# Smoothiepanel.net
KiCad netlist of a schematic drawn in EAGLE
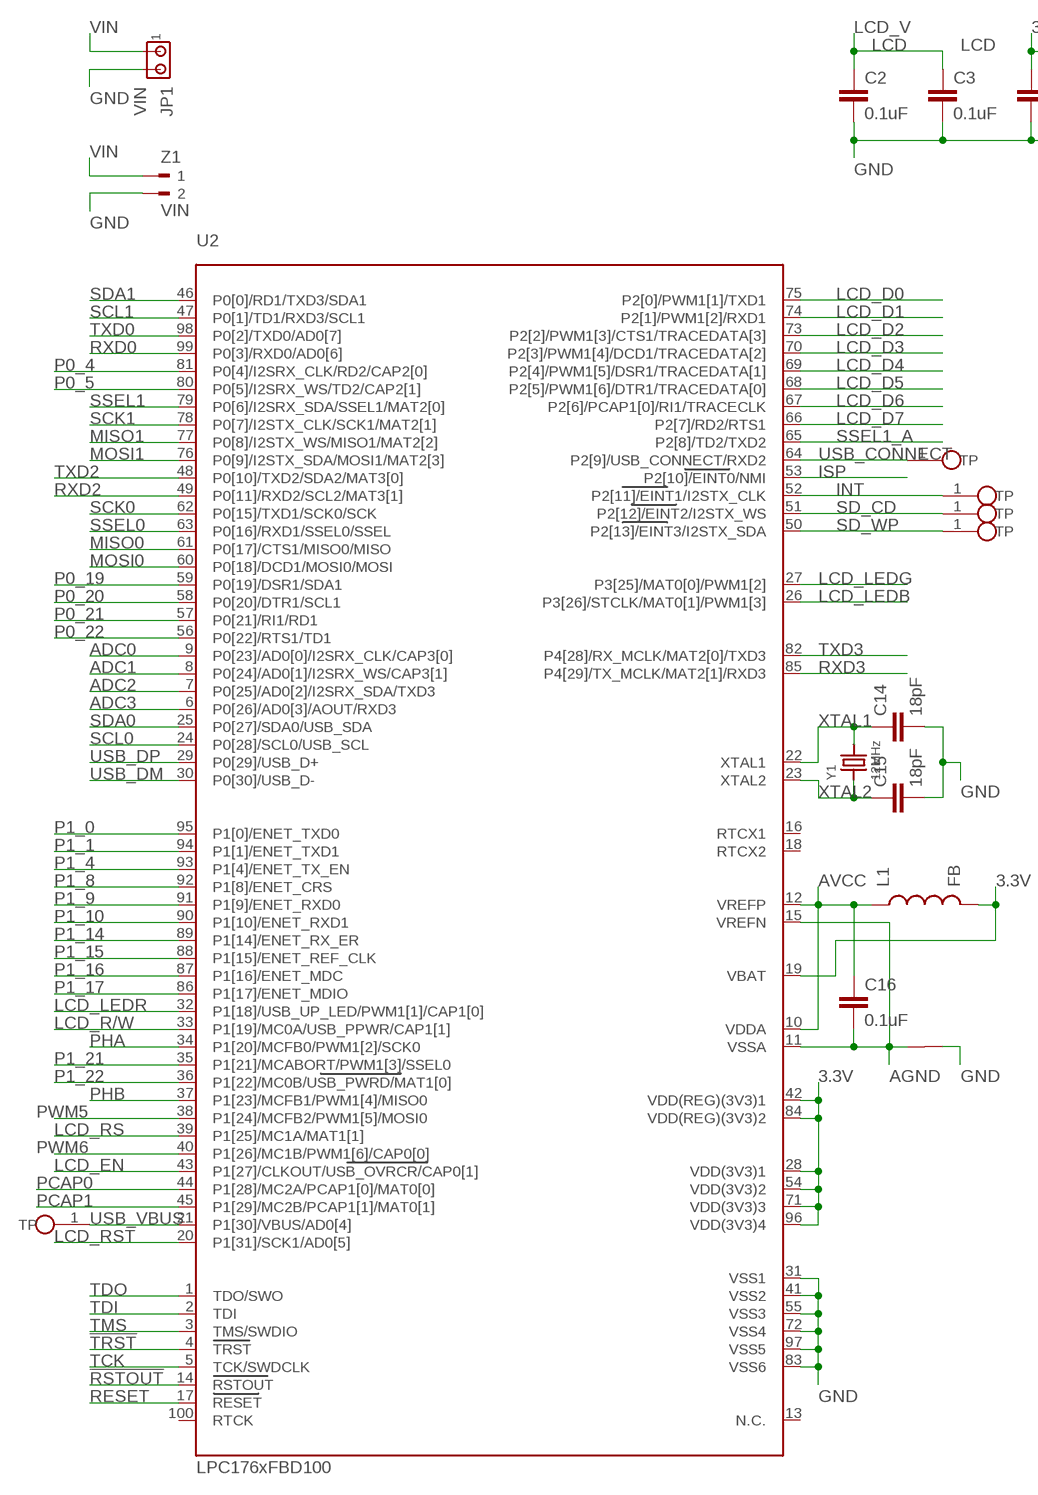
[diagram p0: schematic, sheet 1, part 1 of 2]
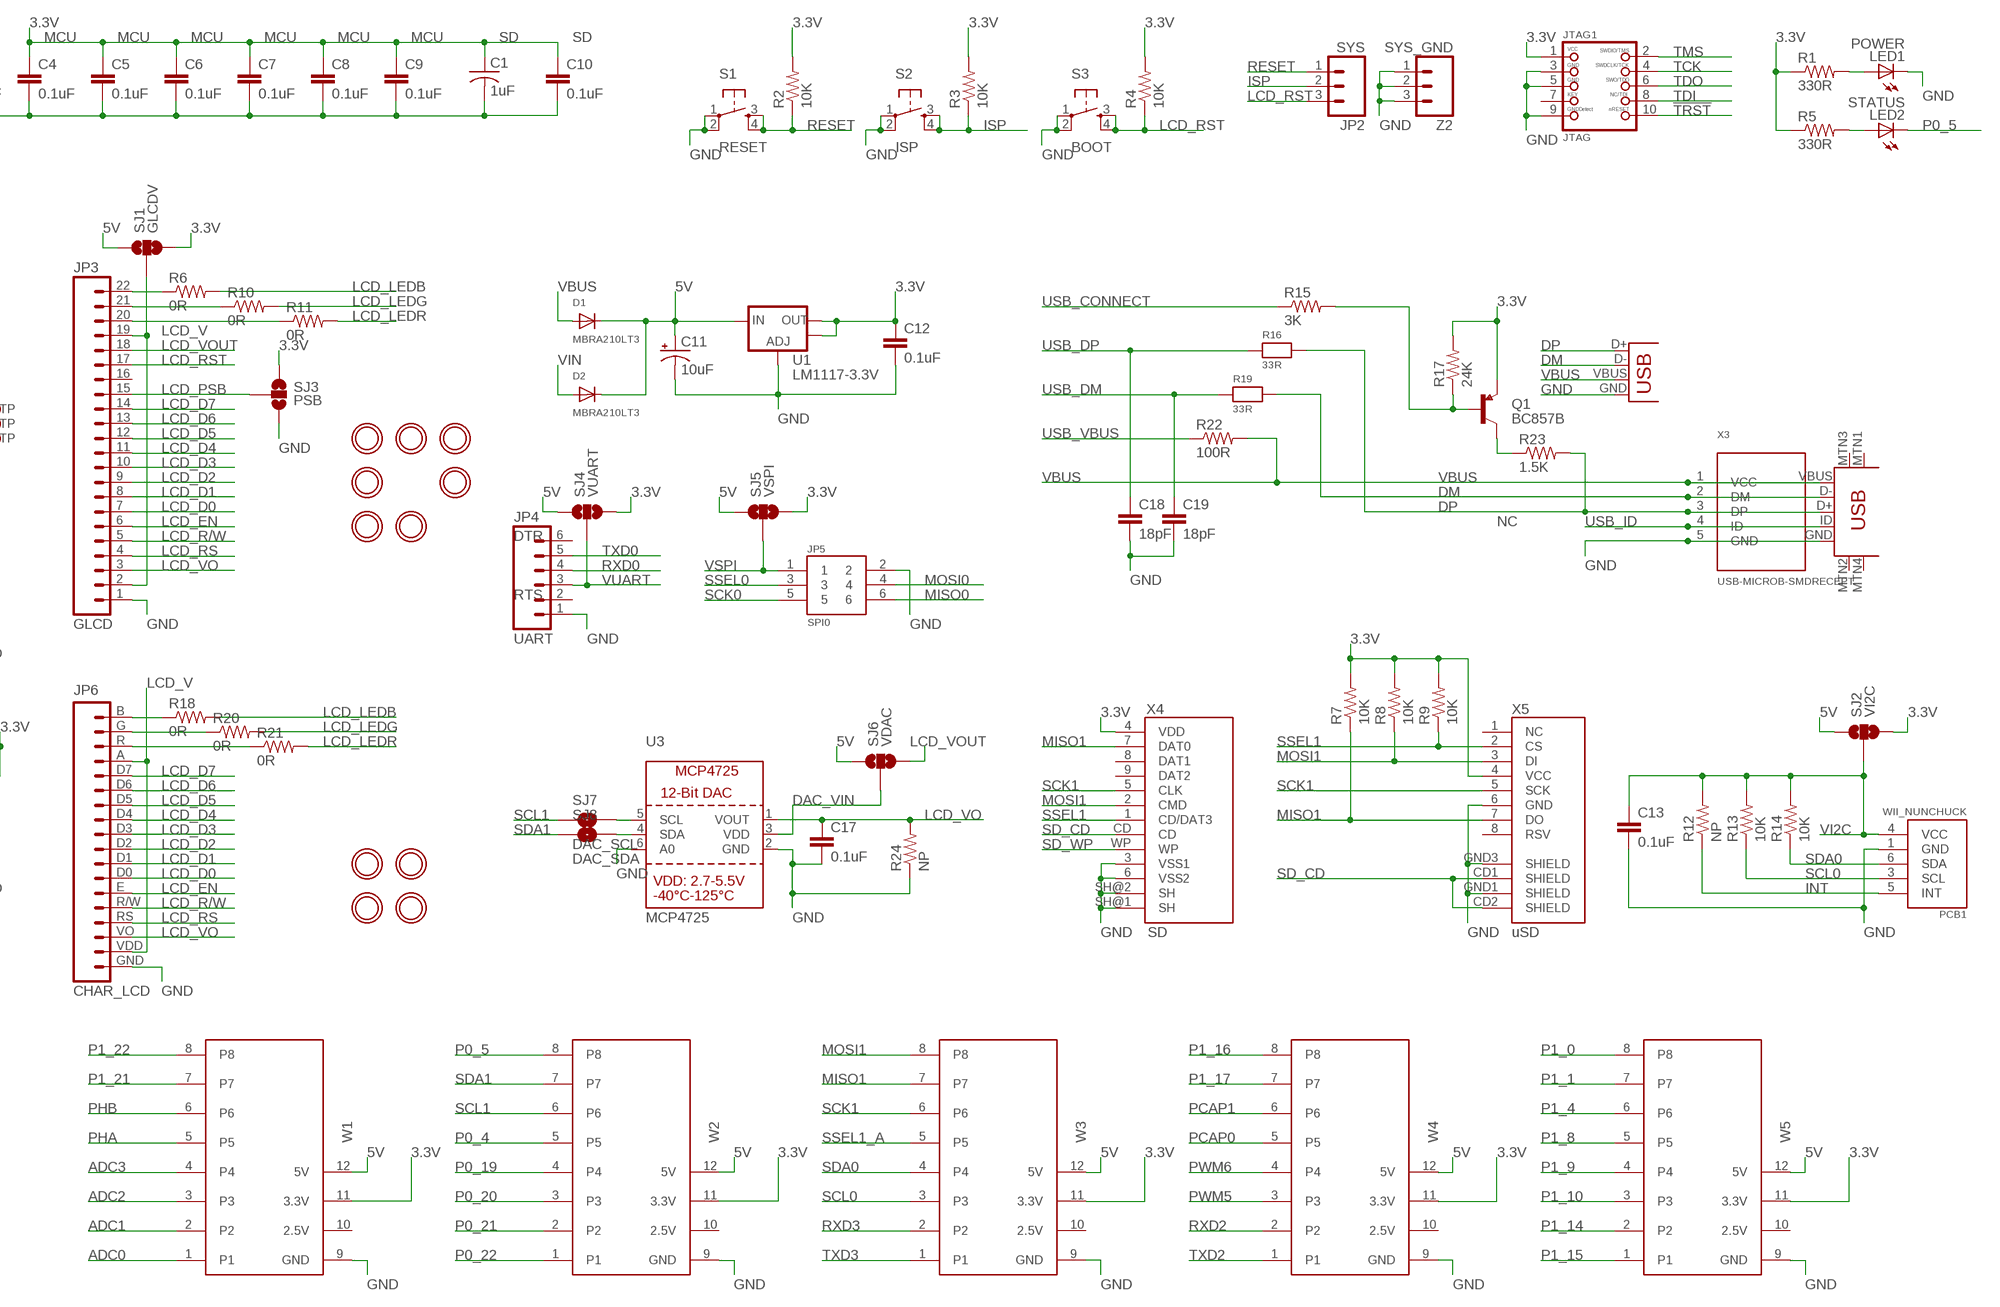
[diagram p1: schematic, sheet 1, part 2 of 2]

(export (version "E")
  (design (tool "Eeschema 10.0.6"))
  (components
    (comp (ref "C1")
      (value "1uF")
      (footprint "eagle-import:C0805")
      (libsource (lib "eagle-import") (part "C-USC0805"))
    )
    (comp (ref "C2")
      (value "0.1uF")
      (footprint "eagle-import:0603-CAP")
      (libsource (lib "eagle-import") (part "CAP0603-CAP"))
    )
    (comp (ref "C3")
      (value "0.1uF")
      (footprint "eagle-import:0603-CAP")
      (libsource (lib "eagle-import") (part "CAP0603-CAP"))
    )
    (comp (ref "C4")
      (value "0.1uF")
      (footprint "eagle-import:0603-CAP")
      (libsource (lib "eagle-import") (part "CAP0603-CAP"))
    )
    (comp (ref "C5")
      (value "0.1uF")
      (footprint "eagle-import:0603-CAP")
      (libsource (lib "eagle-import") (part "CAP0603-CAP"))
    )
    (comp (ref "C6")
      (value "0.1uF")
      (footprint "eagle-import:0603-CAP")
      (libsource (lib "eagle-import") (part "CAP0603-CAP"))
    )
    (comp (ref "C7")
      (value "0.1uF")
      (footprint "eagle-import:0603-CAP")
      (libsource (lib "eagle-import") (part "CAP0603-CAP"))
    )
    (comp (ref "C8")
      (value "0.1uF")
      (footprint "eagle-import:0603-CAP")
      (libsource (lib "eagle-import") (part "CAP0603-CAP"))
    )
    (comp (ref "C9")
      (value "0.1uF")
      (footprint "eagle-import:0603-CAP")
      (libsource (lib "eagle-import") (part "CAP0603-CAP"))
    )
    (comp (ref "C10")
      (value "0.1uF")
      (footprint "eagle-import:0603-CAP")
      (libsource (lib "eagle-import") (part "CAP0603-CAP"))
    )
    (comp (ref "C11")
      (value "10uF")
      (footprint "eagle-import:EIA3216")
      (libsource (lib "eagle-import") (part "CAP_POL1206"))
    )
    (comp (ref "C12")
      (value "0.1uF")
      (footprint "eagle-import:0603-CAP")
      (libsource (lib "eagle-import") (part "CAP0603-CAP"))
    )
    (comp (ref "C13")
      (value "0.1uF")
      (footprint "eagle-import:0603-CAP")
      (libsource (lib "eagle-import") (part "CAP0603-CAP"))
    )
    (comp (ref "C14")
      (value "18pF")
      (footprint "eagle-import:0603-CAP")
      (libsource (lib "eagle-import") (part "SparkFun-Passives_CAP0603-CAP"))
    )
    (comp (ref "C15")
      (value "18pF")
      (footprint "eagle-import:0603-CAP")
      (libsource (lib "eagle-import") (part "SparkFun-Passives_CAP0603-CAP"))
    )
    (comp (ref "C16")
      (value "0.1uF")
      (footprint "eagle-import:0603-CAP")
      (libsource (lib "eagle-import") (part "CAP0603-CAP"))
    )
    (comp (ref "C17")
      (value "0.1uF")
      (footprint "eagle-import:0603-CAP")
      (libsource (lib "eagle-import") (part "CAP0603-CAP"))
    )
    (comp (ref "C18")
      (value "18pF")
      (footprint "eagle-import:0603-CAP")
      (libsource (lib "eagle-import") (part "CAP0603-CAP"))
    )
    (comp (ref "C19")
      (value "18pF")
      (footprint "eagle-import:0603-CAP")
      (libsource (lib "eagle-import") (part "CAP0603-CAP"))
    )
    (comp (ref "D1")
      (value "MBRA210LT3")
      (footprint "eagle-import:SMADIODE")
      (libsource (lib "eagle-import") (part "DIODESMA"))
    )
    (comp (ref "D2")
      (value "MBRA210LT3")
      (footprint "eagle-import:SMADIODE")
      (libsource (lib "eagle-import") (part "DIODESMA"))
    )
    (comp (ref "JP1")
      (value "VIN")
      (footprint "eagle-import:10X02MTA")
      (libsource (lib "eagle-import") (part "MTA02-100"))
    )
    (comp (ref "JP2")
      (value "SYS")
      (footprint "eagle-import:1X03")
      (libsource (lib "eagle-import") (part "M03PTH"))
    )
    (comp (ref "JP3")
      (value "GLCD")
      (footprint "eagle-import:1X22")
      (libsource (lib "eagle-import") (part "M22"))
    )
    (comp (ref "JP4")
      (value "UART")
      (footprint "eagle-import:1X06")
      (libsource (lib "eagle-import") (part "M06SIP"))
    )
    (comp (ref "JP5")
      (value "SPI0")
      (footprint "eagle-import:2X3-SHROUDED")
      (libsource (lib "eagle-import") (part "M03X2"))
    )
    (comp (ref "JP6")
      (value "CHAR_LCD")
      (footprint "eagle-import:TEXT_LCD")
      (libsource (lib "eagle-import") (part "LCD_TEXT"))
    )
    (comp (ref "JTAG1")
      (value "JTAG")
      (footprint "eagle-import:2X05_1.27MM_SMT")
      (libsource (lib "eagle-import") (part "JTAG-CORTEXM3"))
    )
    (comp (ref "L1")
      (value "FB")
      (footprint "eagle-import:0603")
      (libsource (lib "eagle-import") (part "INDUCTOR0603"))
    )
    (comp (ref "LED1")
      (value "POWER")
      (footprint "eagle-import:LED-0603")
      (libsource (lib "eagle-import") (part "LED0603"))
    )
    (comp (ref "LED2")
      (value "STATUS")
      (footprint "eagle-import:LED-0603")
      (libsource (lib "eagle-import") (part "LED0603"))
    )
    (comp (ref "MH1")
      (value "MOUNTINGHOLE2.5_THICK")
      (footprint "eagle-import:MOUNTINGHOLE_2.5_PLATED_THICK")
      (libsource (lib "eagle-import") (part "MOUNTINGHOLE2.5_THICK"))
    )
    (comp (ref "MH2")
      (value "MOUNTINGHOLE2.5_THICK")
      (footprint "eagle-import:MOUNTINGHOLE_2.5_PLATED_THICK")
      (libsource (lib "eagle-import") (part "MOUNTINGHOLE2.5_THICK"))
    )
    (comp (ref "MH3")
      (value "MOUNTINGHOLE2.5_THICK")
      (footprint "eagle-import:MOUNTINGHOLE_2.5_PLATED_THICK")
      (libsource (lib "eagle-import") (part "MOUNTINGHOLE2.5_THICK"))
    )
    (comp (ref "MH4")
      (value "MOUNTINGHOLE2.5_THICK")
      (footprint "eagle-import:MOUNTINGHOLE_2.5_PLATED_THICK")
      (libsource (lib "eagle-import") (part "MOUNTINGHOLE2.5_THICK"))
    )
    (comp (ref "MH5")
      (value "MOUNTINGHOLE2.5_THICK")
      (footprint "eagle-import:MOUNTINGHOLE_2.5_PLATED_THICK")
      (libsource (lib "eagle-import") (part "MOUNTINGHOLE2.5_THICK"))
    )
    (comp (ref "MH6")
      (value "MOUNTINGHOLE2.5_THICK")
      (footprint "eagle-import:MOUNTINGHOLE_2.5_PLATED_THICK")
      (libsource (lib "eagle-import") (part "MOUNTINGHOLE2.5_THICK"))
    )
    (comp (ref "MH7")
      (value "MOUNTINGHOLE2.5_THICK")
      (footprint "eagle-import:MOUNTINGHOLE_2.5_PLATED_THICK")
      (libsource (lib "eagle-import") (part "MOUNTINGHOLE2.5_THICK"))
    )
    (comp (ref "MH8")
      (value "MOUNTINGHOLE3.0THIN")
      (footprint "eagle-import:MOUNTINGHOLE_3.0_PLATEDTHIN")
      (libsource (lib "eagle-import") (part "MOUNTINGHOLE3.0THIN"))
    )
    (comp (ref "MH9")
      (value "MOUNTINGHOLE3.0THIN")
      (footprint "eagle-import:MOUNTINGHOLE_3.0_PLATEDTHIN")
      (libsource (lib "eagle-import") (part "MOUNTINGHOLE3.0THIN"))
    )
    (comp (ref "MH10")
      (value "MOUNTINGHOLE3.0THIN")
      (footprint "eagle-import:MOUNTINGHOLE_3.0_PLATEDTHIN")
      (libsource (lib "eagle-import") (part "MOUNTINGHOLE3.0THIN"))
    )
    (comp (ref "MH11")
      (value "MOUNTINGHOLE3.0THIN")
      (footprint "eagle-import:MOUNTINGHOLE_3.0_PLATEDTHIN")
      (libsource (lib "eagle-import") (part "MOUNTINGHOLE3.0THIN"))
    )
    (comp (ref "N1")
      (value "NET_LINK")
      (footprint "eagle-import:NET_LINK")
      (libsource (lib "eagle-import") (part "NET_LINK"))
    )
    (comp (ref "PCB1")
      (value "WII_NUNCHUCK")
      (footprint "eagle-import:WII_NUNCHUCK")
      (libsource (lib "eagle-import") (part "WII_NUNCHUCK"))
    )
    (comp (ref "Q1")
      (value "BC857B")
      (footprint "eagle-import:SOT23-3")
      (libsource (lib "eagle-import") (part "TRANSISTOR_PNPSMD"))
    )
    (comp (ref "R1")
      (value "330R")
      (footprint "eagle-import:0603-RES")
      (libsource (lib "eagle-import") (part "SparkFun-Resistors_RESISTOR0603-RES"))
    )
    (comp (ref "R2")
      (value "10K")
      (footprint "eagle-import:0603-RES")
      (libsource (lib "eagle-import") (part "SparkFun-Resistors_RESISTOR0603-RES"))
    )
    (comp (ref "R3")
      (value "10K")
      (footprint "eagle-import:0603-RES")
      (libsource (lib "eagle-import") (part "SparkFun-Resistors_RESISTOR0603-RES"))
    )
    (comp (ref "R4")
      (value "10K")
      (footprint "eagle-import:0603-RES")
      (libsource (lib "eagle-import") (part "SparkFun-Resistors_RESISTOR0603-RES"))
    )
    (comp (ref "R5")
      (value "330R")
      (footprint "eagle-import:0603-RES")
      (libsource (lib "eagle-import") (part "SparkFun-Resistors_RESISTOR0603-RES"))
    )
    (comp (ref "R6")
      (value "0R")
      (footprint "eagle-import:0603-RES")
      (libsource (lib "eagle-import") (part "SparkFun-Resistors_RESISTOR0603-RES"))
    )
    (comp (ref "R7")
      (value "10K")
      (footprint "eagle-import:0603-RES")
      (libsource (lib "eagle-import") (part "SparkFun-Resistors_RESISTOR0603-RES"))
    )
    (comp (ref "R8")
      (value "10K")
      (footprint "eagle-import:0603-RES")
      (libsource (lib "eagle-import") (part "SparkFun-Resistors_RESISTOR0603-RES"))
    )
    (comp (ref "R9")
      (value "10K")
      (footprint "eagle-import:0603-RES")
      (libsource (lib "eagle-import") (part "SparkFun-Resistors_RESISTOR0603-RES"))
    )
    (comp (ref "R10")
      (value "0R")
      (footprint "eagle-import:0603-RES")
      (libsource (lib "eagle-import") (part "SparkFun-Resistors_RESISTOR0603-RES"))
    )
    (comp (ref "R11")
      (value "0R")
      (footprint "eagle-import:0603-RES")
      (libsource (lib "eagle-import") (part "SparkFun-Resistors_RESISTOR0603-RES"))
    )
    (comp (ref "R12")
      (value "NP")
      (footprint "eagle-import:0603-RES")
      (libsource (lib "eagle-import") (part "RESISTOR0603-RES"))
    )
    (comp (ref "R13")
      (value "10K")
      (footprint "eagle-import:0603-RES")
      (libsource (lib "eagle-import") (part "SparkFun-Resistors_RESISTOR0603-RES"))
    )
    (comp (ref "R14")
      (value "10K")
      (footprint "eagle-import:0603-RES")
      (libsource (lib "eagle-import") (part "SparkFun-Resistors_RESISTOR0603-RES"))
    )
    (comp (ref "R15")
      (value "3K")
      (footprint "eagle-import:0603-RES")
      (libsource (lib "eagle-import") (part "SparkFun-Resistors_RESISTOR0603-RES"))
    )
    (comp (ref "R16")
      (value "33R")
      (footprint "eagle-import:_0603MP")
      (libsource (lib "eagle-import") (part "RESISTOR_0603MP"))
    )
    (comp (ref "R17")
      (value "24K")
      (footprint "eagle-import:0603-RES")
      (libsource (lib "eagle-import") (part "SparkFun-Resistors_RESISTOR0603-RES"))
    )
    (comp (ref "R18")
      (value "0R")
      (footprint "eagle-import:0603-RES")
      (libsource (lib "eagle-import") (part "RESISTOR0603-RES"))
    )
    (comp (ref "R19")
      (value "33R")
      (footprint "eagle-import:_0603MP")
      (libsource (lib "eagle-import") (part "RESISTOR_0603MP"))
    )
    (comp (ref "R20")
      (value "0R")
      (footprint "eagle-import:0603-RES")
      (libsource (lib "eagle-import") (part "RESISTOR0603-RES"))
    )
    (comp (ref "R21")
      (value "0R")
      (footprint "eagle-import:0603-RES")
      (libsource (lib "eagle-import") (part "RESISTOR0603-RES"))
    )
    (comp (ref "R22")
      (value "100R")
      (footprint "eagle-import:0603-RES")
      (libsource (lib "eagle-import") (part "SparkFun-Resistors_RESISTOR0603-RES"))
    )
    (comp (ref "R23")
      (value "1.5K")
      (footprint "eagle-import:0603-RES")
      (libsource (lib "eagle-import") (part "SparkFun-Resistors_RESISTOR0603-RES"))
    )
    (comp (ref "R24")
      (value "NP")
      (footprint "eagle-import:0603-RES")
      (libsource (lib "eagle-import") (part "SparkFun-Resistors_RESISTOR0603-RES"))
    )
    (comp (ref "S1")
      (value "RESET")
      (footprint "eagle-import:TACTILE_SWITCH_SMD")
      (libsource (lib "eagle-import") (part "TAC_SWITCHSMD"))
    )
    (comp (ref "S2")
      (value "ISP")
      (footprint "eagle-import:TACTILE_SWITCH_SMD")
      (libsource (lib "eagle-import") (part "TAC_SWITCHSMD"))
    )
    (comp (ref "S3")
      (value "BOOT")
      (footprint "eagle-import:TACTILE_SWITCH_SMD")
      (libsource (lib "eagle-import") (part "TAC_SWITCHSMD"))
    )
    (comp (ref "SJ1")
      (value "GLCDV")
      (footprint "eagle-import:SJ_3")
      (libsource (lib "eagle-import") (part "SOLDERJUMPER_2WAYS"))
    )
    (comp (ref "SJ2")
      (value "VI2C")
      (footprint "eagle-import:SJ_3")
      (libsource (lib "eagle-import") (part "SparkFun-Passives_SOLDERJUMPER_2WAYS"))
    )
    (comp (ref "SJ3")
      (value "PSB")
      (footprint "eagle-import:SJ_3")
      (libsource (lib "eagle-import") (part "SOLDERJUMPER_2WAYS"))
    )
    (comp (ref "SJ4")
      (value "VUART")
      (footprint "eagle-import:SJ_3")
      (libsource (lib "eagle-import") (part "SOLDERJUMPER_2WAYS"))
    )
    (comp (ref "SJ5")
      (value "VSPI")
      (footprint "eagle-import:SJ_3")
      (libsource (lib "eagle-import") (part "SOLDERJUMPER_2WAYS"))
    )
    (comp (ref "SJ6")
      (value "VDAC")
      (footprint "eagle-import:SJ_3")
      (libsource (lib "eagle-import") (part "SOLDERJUMPER_2WAYS"))
    )
    (comp (ref "SJ7")
      (value "DAC_SCL")
      (footprint "eagle-import:SJ_2S-TRACE")
      (libsource (lib "eagle-import") (part "SOLDERJUMPERTRACE"))
    )
    (comp (ref "SJ8")
      (value "DAC_SDA")
      (footprint "eagle-import:SJ_2S-TRACE")
      (libsource (lib "eagle-import") (part "SOLDERJUMPERTRACE"))
    )
    (comp (ref "TP1")
      (value "TPAD1.5")
      (footprint "eagle-import:TPAD-1.5")
      (libsource (lib "eagle-import") (part "TPAD1.5"))
    )
    (comp (ref "TP3")
      (value "TPAD1.5")
      (footprint "eagle-import:TPAD-1.5")
      (libsource (lib "eagle-import") (part "TPAD1.5"))
    )
    (comp (ref "TP4")
      (value "TPAD1.5")
      (footprint "eagle-import:TPAD-1.5")
      (libsource (lib "eagle-import") (part "TPAD1.5"))
    )
    (comp (ref "TP5")
      (value "TPAD1.5")
      (footprint "eagle-import:TPAD-1.5")
      (libsource (lib "eagle-import") (part "TPAD1.5"))
    )
    (comp (ref "TP6")
      (value "TPAD1.5")
      (footprint "eagle-import:TPAD-1.5")
      (libsource (lib "eagle-import") (part "TPAD1.5"))
    )
    (comp (ref "U1")
      (value "LM1117-3.3V")
      (footprint "eagle-import:SOT223")
      (libsource (lib "eagle-import") (part "V_REG_LM1117SOT223"))
    )
    (comp (ref "U2")
      (value "LPC176xFBD100")
      (footprint "eagle-import:LQFP100")
      (libsource (lib "eagle-import") (part "LPC1768"))
    )
    (comp (ref "U3")
      (value "MCP4725")
      (footprint "eagle-import:SOT23-6")
      (libsource (lib "eagle-import") (part "DAC_MCP4725"))
    )
    (comp (ref "W1")
      (value "WING1")
      (footprint "eagle-import:PAPILIO-WING-8BITS-F")
      (libsource (lib "eagle-import") (part "PAPILIO-WING-8BITSF"))
    )
    (comp (ref "W2")
      (value "WING2")
      (footprint "eagle-import:PAPILIO-WING-8BITS-F")
      (libsource (lib "eagle-import") (part "PAPILIO-WING-8BITSF"))
    )
    (comp (ref "W3")
      (value "WING3")
      (footprint "eagle-import:PAPILIO-WING-8BITS-F")
      (libsource (lib "eagle-import") (part "PAPILIO-WING-8BITSF"))
    )
    (comp (ref "W4")
      (value "WING4")
      (footprint "eagle-import:PAPILIO-WING-8BITS-F")
      (libsource (lib "eagle-import") (part "PAPILIO-WING-8BITSF"))
    )
    (comp (ref "W5")
      (value "WING5")
      (footprint "eagle-import:PAPILIO-WING-8BITS-F")
      (libsource (lib "eagle-import") (part "PAPILIO-WING-8BITSF"))
    )
    (comp (ref "X1")
      (value "USB-B")
      (footprint "eagle-import:USB-B-PTH")
      (libsource (lib "eagle-import") (part "USBPTH"))
    )
    (comp (ref "X2")
      (value "mUSB")
      (footprint "eagle-import:USB-MINIB")
      (libsource (lib "eagle-import") (part "USB-MINIB-5PIN"))
    )
    (comp (ref "X3")
      (value "USB-MICROB-SMDRECEPT")
      (footprint "eagle-import:USB-MICROB-RECEPT")
      (libsource (lib "eagle-import") (part "USB-MICROB-SMDRECEPT"))
    )
    (comp (ref "X4")
      (value "SD")
      (footprint "eagle-import:SDCARD_4UCONN")
      (libsource (lib "eagle-import") (part "SD_CARD_SOCKET4UCON"))
    )
    (comp (ref "X5")
      (value "uSD")
      (footprint "eagle-import:MICRO-SD-SOCKET-PP")
      (libsource (lib "eagle-import") (part "USD-SOCKETNEW"))
    )
    (comp (ref "Y1")
      (value "12MHz")
      (footprint "eagle-import:CRYSTAL_3.2X2.5")
      (libsource (lib "eagle-import") (part "CRYSTALTHIN"))
    )
    (comp (ref "Z1")
      (value "VIN")
      (footprint "eagle-import:180-2")
      (libsource (lib "eagle-import") (part "180-2"))
    )
    (comp (ref "Z2")
      (value "SYS_GND")
      (footprint "eagle-import:1X03")
      (libsource (lib "eagle-import") (part "M03PTH"))
    )
  )
  (nets
    (net (code "1") (name "/3.3V") (class "Default")
      (node (ref "C1") (pin "1") (pinfunction "1_1") (pintype "passive"))
      (node (ref "C10") (pin "1") (pinfunction "1_1") (pintype "passive"))
      (node (ref "C12") (pin "1") (pinfunction "1_1") (pintype "passive"))
      (node (ref "C4") (pin "1") (pinfunction "1_1") (pintype "passive"))
      (node (ref "C5") (pin "1") (pinfunction "1_1") (pintype "passive"))
      (node (ref "C6") (pin "1") (pinfunction "1_1") (pintype "passive"))
      (node (ref "C7") (pin "1") (pinfunction "1_1") (pintype "passive"))
      (node (ref "C8") (pin "1") (pinfunction "1_1") (pintype "passive"))
      (node (ref "C9") (pin "1") (pinfunction "1_1") (pintype "passive"))
      (node (ref "JTAG1") (pin "1") (pinfunction "1_1") (pintype "passive"))
      (node (ref "L1") (pin "2") (pinfunction "2_2") (pintype "passive"))
      (node (ref "Q1") (pin "2") (pinfunction "E_2") (pintype "passive"))
      (node (ref "R1") (pin "1") (pinfunction "1_1") (pintype "passive"))
      (node (ref "R17") (pin "2") (pinfunction "2_2") (pintype "passive"))
      (node (ref "R2") (pin "2") (pinfunction "2_2") (pintype "passive"))
      (node (ref "R3") (pin "2") (pinfunction "2_2") (pintype "passive"))
      (node (ref "R4") (pin "2") (pinfunction "2_2") (pintype "passive"))
      (node (ref "R5") (pin "1") (pinfunction "1_1") (pintype "passive"))
      (node (ref "R7") (pin "2") (pinfunction "2_2") (pintype "passive"))
      (node (ref "R8") (pin "2") (pinfunction "2_2") (pintype "passive"))
      (node (ref "R9") (pin "2") (pinfunction "2_2") (pintype "passive"))
      (node (ref "SJ1") (pin "3") (pinfunction "3_3") (pintype "passive"))
      (node (ref "SJ2") (pin "3") (pinfunction "3_3") (pintype "passive"))
      (node (ref "SJ3") (pin "1") (pinfunction "1_1") (pintype "passive"))
      (node (ref "SJ4") (pin "3") (pinfunction "3_3") (pintype "passive"))
      (node (ref "SJ5") (pin "3") (pinfunction "3_3") (pintype "passive"))
      (node (ref "U1") (pin "2") (pinfunction "OUT_2") (pintype "output"))
      (node (ref "U1") (pin "4") (pinfunction "OUT_4") (pintype "output"))
      (node (ref "U2") (pin "19") (pinfunction "VBAT_19") (pintype "power_in"))
      (node (ref "U2") (pin "28") (pinfunction "VDD(3V3)1_28") (pintype "power_in"))
      (node (ref "U2") (pin "42") (pinfunction "VDD(REG)(3V3)1_42") (pintype "power_in"))
      (node (ref "U2") (pin "54") (pinfunction "VDD(3V3)2_54") (pintype "power_in"))
      (node (ref "U2") (pin "71") (pinfunction "VDD(3V3)3_71") (pintype "power_in"))
      (node (ref "U2") (pin "84") (pinfunction "VDD(REG)(3V3)2_84") (pintype "power_in"))
      (node (ref "U2") (pin "96") (pinfunction "VDD(3V3)4_96") (pintype "power_in"))
      (node (ref "W1") (pin "11") (pinfunction "3.3V_11") (pintype "bidirectional"))
      (node (ref "W2") (pin "11") (pinfunction "3.3V_11") (pintype "bidirectional"))
      (node (ref "W3") (pin "11") (pinfunction "3.3V_11") (pintype "bidirectional"))
      (node (ref "W4") (pin "11") (pinfunction "3.3V_11") (pintype "bidirectional"))
      (node (ref "W5") (pin "11") (pinfunction "3.3V_11") (pintype "bidirectional"))
      (node (ref "X4") (pin "4") (pinfunction "VDD_4") (pintype "power_in"))
      (node (ref "X5") (pin "4") (pinfunction "VCC_4") (pintype "bidirectional"))
    )
    (net (code "2") (name "/5V") (class "Default")
      (node (ref "C11") (pin "A") (pinfunction "+_A") (pintype "passive"))
      (node (ref "D1") (pin "C") (pinfunction "C_C") (pintype "passive"))
      (node (ref "D2") (pin "C") (pinfunction "C_C") (pintype "passive"))
      (node (ref "SJ1") (pin "1") (pinfunction "1_1") (pintype "passive"))
      (node (ref "SJ2") (pin "1") (pinfunction "1_1") (pintype "passive"))
      (node (ref "SJ4") (pin "1") (pinfunction "1_1") (pintype "passive"))
      (node (ref "SJ5") (pin "1") (pinfunction "1_1") (pintype "passive"))
      (node (ref "SJ6") (pin "1") (pinfunction "1_1") (pintype "passive"))
      (node (ref "U1") (pin "3") (pinfunction "IN_3") (pintype "input"))
      (node (ref "W1") (pin "12") (pinfunction "5V_12") (pintype "bidirectional"))
      (node (ref "W2") (pin "12") (pinfunction "5V_12") (pintype "bidirectional"))
      (node (ref "W3") (pin "12") (pinfunction "5V_12") (pintype "bidirectional"))
      (node (ref "W4") (pin "12") (pinfunction "5V_12") (pintype "bidirectional"))
      (node (ref "W5") (pin "12") (pinfunction "5V_12") (pintype "bidirectional"))
    )
    (net (code "3") (name "/ADC0") (class "Default")
      (node (ref "U2") (pin "9") (pinfunction "P0[23]/AD0[0]/I2SRX_CLK/CAP3[0]_9") (pintype "bidirectional"))
      (node (ref "W1") (pin "1") (pinfunction "P1_1") (pintype "bidirectional"))
    )
    (net (code "4") (name "/ADC1") (class "Default")
      (node (ref "U2") (pin "8") (pinfunction "P0[24]/AD0[1]/I2SRX_WS/CAP3[1]_8") (pintype "bidirectional"))
      (node (ref "W1") (pin "2") (pinfunction "P2_2") (pintype "bidirectional"))
    )
    (net (code "5") (name "/ADC2") (class "Default")
      (node (ref "U2") (pin "7") (pinfunction "P0[25]/AD0[2]/I2SRX_SDA/TXD3_7") (pintype "bidirectional"))
      (node (ref "W1") (pin "3") (pinfunction "P3_3") (pintype "bidirectional"))
    )
    (net (code "6") (name "/ADC3") (class "Default")
      (node (ref "U2") (pin "6") (pinfunction "P0[26]/AD0[3]/AOUT/RXD3_6") (pintype "bidirectional"))
      (node (ref "W1") (pin "4") (pinfunction "P4_4") (pintype "bidirectional"))
    )
    (net (code "7") (name "/AGND") (class "Default")
      (node (ref "C16") (pin "2") (pinfunction "2_2") (pintype "passive"))
      (node (ref "N1") (pin "P$1") (pinfunction "P$1_P$1") (pintype "bidirectional"))
      (node (ref "U2") (pin "11") (pinfunction "VSSA_11") (pintype "power_in"))
      (node (ref "U2") (pin "15") (pinfunction "VREFN_15") (pintype "power_in"))
    )
    (net (code "8") (name "/AVCC") (class "Default")
      (node (ref "C16") (pin "1") (pinfunction "1_1") (pintype "passive"))
      (node (ref "L1") (pin "1") (pinfunction "1_1") (pintype "passive"))
      (node (ref "U2") (pin "10") (pinfunction "VDDA_10") (pintype "power_in"))
      (node (ref "U2") (pin "12") (pinfunction "VREFP_12") (pintype "power_in"))
    )
    (net (code "9") (name "/DAC_VIN") (class "Default")
      (node (ref "SJ6") (pin "2") (pinfunction "2_2") (pintype "passive"))
      (node (ref "U3") (pin "3") (pinfunction "VDD_3") (pintype "power_in"))
    )
    (net (code "10") (name "/DM") (class "Default")
      (node (ref "R19") (pin "2") (pinfunction "2_2") (pintype "passive"))
      (node (ref "X1") (pin "D-") (pinfunction "D-_D-") (pintype "bidirectional"))
      (node (ref "X2") (pin "D-") (pinfunction "D-_D-") (pintype "bidirectional"))
      (node (ref "X3") (pin "2") (pinfunction "DM_2") (pintype "bidirectional"))
    )
    (net (code "11") (name "/DP") (class "Default")
      (node (ref "R16") (pin "2") (pinfunction "2_2") (pintype "passive"))
      (node (ref "R23") (pin "2") (pinfunction "2_2") (pintype "passive"))
      (node (ref "X1") (pin "D+") (pinfunction "D+_D+") (pintype "bidirectional"))
      (node (ref "X2") (pin "D+") (pinfunction "D+_D+") (pintype "bidirectional"))
      (node (ref "X3") (pin "3") (pinfunction "DP_3") (pintype "bidirectional"))
    )
    (net (code "12") (name "/GND") (class "Default")
      (node (ref "C1") (pin "2") (pinfunction "2_2") (pintype "passive"))
      (node (ref "C10") (pin "2") (pinfunction "2_2") (pintype "passive"))
      (node (ref "C11") (pin "C") (pinfunction "-_C") (pintype "passive"))
      (node (ref "C12") (pin "2") (pinfunction "2_2") (pintype "passive"))
      (node (ref "C13") (pin "2") (pinfunction "2_2") (pintype "passive"))
      (node (ref "C14") (pin "2") (pinfunction "2_2") (pintype "passive"))
      (node (ref "C15") (pin "2") (pinfunction "2_2") (pintype "passive"))
      (node (ref "C17") (pin "2") (pinfunction "2_2") (pintype "passive"))
      (node (ref "C18") (pin "2") (pinfunction "2_2") (pintype "passive"))
      (node (ref "C19") (pin "2") (pinfunction "2_2") (pintype "passive"))
      (node (ref "C2") (pin "2") (pinfunction "2_2") (pintype "passive"))
      (node (ref "C3") (pin "2") (pinfunction "2_2") (pintype "passive"))
      (node (ref "C4") (pin "2") (pinfunction "2_2") (pintype "passive"))
      (node (ref "C5") (pin "2") (pinfunction "2_2") (pintype "passive"))
      (node (ref "C6") (pin "2") (pinfunction "2_2") (pintype "passive"))
      (node (ref "C7") (pin "2") (pinfunction "2_2") (pintype "passive"))
      (node (ref "C8") (pin "2") (pinfunction "2_2") (pintype "passive"))
      (node (ref "C9") (pin "2") (pinfunction "2_2") (pintype "passive"))
      (node (ref "JP1") (pin "2") (pinfunction "2_2") (pintype "passive"))
      (node (ref "JP3") (pin "1") (pinfunction "1_1") (pintype "passive"))
      (node (ref "JP4") (pin "1") (pinfunction "1_1") (pintype "passive"))
      (node (ref "JP5") (pin "2") (pinfunction "2_2") (pintype "bidirectional"))
      (node (ref "JP6") (pin "GND") (pinfunction "1_GND") (pintype "passive"))
      (node (ref "JTAG1") (pin "3") (pinfunction "3_3") (pintype "passive"))
      (node (ref "JTAG1") (pin "5") (pinfunction "5_5") (pintype "passive"))
      (node (ref "JTAG1") (pin "9") (pinfunction "9_9") (pintype "passive"))
      (node (ref "LED1") (pin "C") (pinfunction "C_C") (pintype "passive"))
      (node (ref "N1") (pin "P$2") (pinfunction "P$2_P$2") (pintype "bidirectional"))
      (node (ref "PCB1") (pin "1") (pinfunction "GND_1") (pintype "power_in"))
      (node (ref "R24") (pin "1") (pinfunction "1_1") (pintype "passive"))
      (node (ref "S1") (pin "1") (pinfunction "1_1") (pintype "passive"))
      (node (ref "S1") (pin "2") (pinfunction "2_2") (pintype "passive"))
      (node (ref "S2") (pin "1") (pinfunction "1_1") (pintype "passive"))
      (node (ref "S2") (pin "2") (pinfunction "2_2") (pintype "passive"))
      (node (ref "S3") (pin "1") (pinfunction "1_1") (pintype "passive"))
      (node (ref "S3") (pin "2") (pinfunction "2_2") (pintype "passive"))
      (node (ref "SJ3") (pin "3") (pinfunction "3_3") (pintype "passive"))
      (node (ref "U1") (pin "1") (pinfunction "ADJ_1") (pintype "input"))
      (node (ref "U2") (pin "31") (pinfunction "VSS1_31") (pintype "power_in"))
      (node (ref "U2") (pin "41") (pinfunction "VSS2_41") (pintype "power_in"))
      (node (ref "U2") (pin "55") (pinfunction "VSS3_55") (pintype "power_in"))
      (node (ref "U2") (pin "72") (pinfunction "VSS4_72") (pintype "power_in"))
      (node (ref "U2") (pin "83") (pinfunction "VSS6_83") (pintype "power_in"))
      (node (ref "U2") (pin "97") (pinfunction "VSS5_97") (pintype "power_in"))
      (node (ref "U3") (pin "2") (pinfunction "GND_2") (pintype "power_in"))
      (node (ref "U3") (pin "6") (pinfunction "A0_6") (pintype "input"))
      (node (ref "W1") (pin "9") (pinfunction "GND_9") (pintype "bidirectional"))
      (node (ref "W2") (pin "9") (pinfunction "GND_9") (pintype "bidirectional"))
      (node (ref "W3") (pin "9") (pinfunction "GND_9") (pintype "bidirectional"))
      (node (ref "W4") (pin "9") (pinfunction "GND_9") (pintype "bidirectional"))
      (node (ref "W5") (pin "9") (pinfunction "GND_9") (pintype "bidirectional"))
      (node (ref "X1") (pin "GND") (pinfunction "GND_GND") (pintype "bidirectional"))
      (node (ref "X2") (pin "GND") (pinfunction "GND_GND") (pintype "bidirectional"))
      (node (ref "X3") (pin "5") (pinfunction "GND_5") (pintype "bidirectional"))
      (node (ref "X4") (pin "3") (pinfunction "VSS1_3") (pintype "power_in"))
      (node (ref "X4") (pin "6") (pinfunction "VSS2_6") (pintype "power_in"))
      (node (ref "X4") (pin "SH@1") (pinfunction "SH_SH@1") (pintype "bidirectional"))
      (node (ref "X4") (pin "SH@2") (pinfunction "SH_SH@2") (pintype "bidirectional"))
      (node (ref "X5") (pin "6") (pinfunction "GND_6") (pintype "bidirectional"))
      (node (ref "X5") (pin "GND1") (pinfunction "SHIELD_GND1") (pintype "bidirectional"))
      (node (ref "X5") (pin "GND3") (pinfunction "SHIELD_GND3") (pintype "bidirectional"))
      (node (ref "Z1") (pin "2") (pinfunction "2_2") (pintype "passive"))
      (node (ref "Z2") (pin "1") (pinfunction "1_1") (pintype "passive"))
      (node (ref "Z2") (pin "2") (pinfunction "2_2") (pintype "passive"))
      (node (ref "Z2") (pin "3") (pinfunction "3_3") (pintype "passive"))
    )
    (net (code "13") (name "/INT") (class "Default")
      (node (ref "PCB1") (pin "5") (pinfunction "INT_5") (pintype "bidirectional"))
      (node (ref "R12") (pin "1") (pinfunction "1_1") (pintype "passive"))
      (node (ref "TP4") (pin "1") (pinfunction "TP_1") (pintype "bidirectional"))
      (node (ref "U2") (pin "52") (pinfunction "P2[11]/EINT1/I2STX_CLK_52") (pintype "bidirectional"))
    )
    (net (code "14") (name "/ISP") (class "Default")
      (node (ref "JP2") (pin "2") (pinfunction "2_2") (pintype "passive"))
      (node (ref "R3") (pin "1") (pinfunction "1_1") (pintype "passive"))
      (node (ref "S2") (pin "3") (pinfunction "3_3") (pintype "passive"))
      (node (ref "S2") (pin "4") (pinfunction "4_4") (pintype "passive"))
      (node (ref "U2") (pin "53") (pinfunction "P2[10]/EINT0/NMI_53") (pintype "bidirectional"))
    )
    (net (code "15") (name "/LCD_D0") (class "Default")
      (node (ref "JP3") (pin "7") (pinfunction "7_7") (pintype "passive"))
      (node (ref "JP6") (pin "D0") (pinfunction "7_D0") (pintype "passive"))
      (node (ref "U2") (pin "75") (pinfunction "P2[0]/PWM1[1]/TXD1_75") (pintype "bidirectional"))
    )
    (net (code "16") (name "/LCD_D1") (class "Default")
      (node (ref "JP3") (pin "8") (pinfunction "8_8") (pintype "passive"))
      (node (ref "JP6") (pin "D1") (pinfunction "8_D1") (pintype "passive"))
      (node (ref "U2") (pin "74") (pinfunction "P2[1]/PWM1[2]/RXD1_74") (pintype "bidirectional"))
    )
    (net (code "17") (name "/LCD_D2") (class "Default")
      (node (ref "JP3") (pin "9") (pinfunction "9_9") (pintype "passive"))
      (node (ref "JP6") (pin "D2") (pinfunction "9_D2") (pintype "passive"))
      (node (ref "U2") (pin "73") (pinfunction "P2[2]/PWM1[3]/CTS1/TRACEDATA[3]_73") (pintype "bidirectional"))
    )
    (net (code "18") (name "/LCD_D3") (class "Default")
      (node (ref "JP3") (pin "10") (pinfunction "10_10") (pintype "passive"))
      (node (ref "JP6") (pin "D3") (pinfunction "10_D3") (pintype "passive"))
      (node (ref "U2") (pin "70") (pinfunction "P2[3]/PWM1[4]/DCD1/TRACEDATA[2]_70") (pintype "bidirectional"))
    )
    (net (code "19") (name "/LCD_D4") (class "Default")
      (node (ref "JP3") (pin "11") (pinfunction "11_11") (pintype "passive"))
      (node (ref "JP6") (pin "D4") (pinfunction "11_D4") (pintype "passive"))
      (node (ref "U2") (pin "69") (pinfunction "P2[4]/PWM1[5]/DSR1/TRACEDATA[1]_69") (pintype "bidirectional"))
    )
    (net (code "20") (name "/LCD_D5") (class "Default")
      (node (ref "JP3") (pin "12") (pinfunction "12_12") (pintype "passive"))
      (node (ref "JP6") (pin "D5") (pinfunction "12_D5") (pintype "passive"))
      (node (ref "U2") (pin "68") (pinfunction "P2[5]/PWM1[6]/DTR1/TRACEDATA[0]_68") (pintype "bidirectional"))
    )
    (net (code "21") (name "/LCD_D6") (class "Default")
      (node (ref "JP3") (pin "13") (pinfunction "13_13") (pintype "passive"))
      (node (ref "JP6") (pin "D6") (pinfunction "13_D6") (pintype "passive"))
      (node (ref "U2") (pin "67") (pinfunction "P2[6]/PCAP1[0]/RI1/TRACECLK_67") (pintype "bidirectional"))
    )
    (net (code "22") (name "/LCD_D7") (class "Default")
      (node (ref "JP3") (pin "14") (pinfunction "14_14") (pintype "passive"))
      (node (ref "JP6") (pin "D7") (pinfunction "14_D7") (pintype "passive"))
      (node (ref "U2") (pin "66") (pinfunction "P2[7]/RD2/RTS1_66") (pintype "bidirectional"))
    )
    (net (code "23") (name "/LCD_EN") (class "Default")
      (node (ref "JP3") (pin "6") (pinfunction "6_6") (pintype "passive"))
      (node (ref "JP6") (pin "E") (pinfunction "6_E") (pintype "passive"))
      (node (ref "U2") (pin "43") (pinfunction "P1[27]/CLKOUT/USB_OVRCR/CAP0[1]_43") (pintype "bidirectional"))
    )
    (net (code "24") (name "/LCD_LEDB") (class "Default")
      (node (ref "R18") (pin "2") (pinfunction "2_2") (pintype "passive"))
      (node (ref "R6") (pin "2") (pinfunction "2_2") (pintype "passive"))
      (node (ref "U2") (pin "26") (pinfunction "P3[26]/STCLK/MAT0[1]/PWM1[3]_26") (pintype "bidirectional"))
    )
    (net (code "25") (name "/LCD_LEDG") (class "Default")
      (node (ref "R10") (pin "2") (pinfunction "2_2") (pintype "passive"))
      (node (ref "R20") (pin "2") (pinfunction "2_2") (pintype "passive"))
      (node (ref "U2") (pin "27") (pinfunction "P3[25]/MAT0[0]/PWM1[2]_27") (pintype "bidirectional"))
    )
    (net (code "26") (name "/LCD_LEDR") (class "Default")
      (node (ref "R11") (pin "2") (pinfunction "2_2") (pintype "passive"))
      (node (ref "R21") (pin "2") (pinfunction "2_2") (pintype "passive"))
      (node (ref "U2") (pin "32") (pinfunction "P1[18]/USB_UP_LED/PWM1[1]/CAP1[0]_32") (pintype "bidirectional"))
    )
    (net (code "27") (name "/LCD_PSB") (class "Default")
      (node (ref "JP3") (pin "15") (pinfunction "15_15") (pintype "passive"))
      (node (ref "SJ3") (pin "2") (pinfunction "2_2") (pintype "passive"))
    )
    (net (code "28") (name "/LCD_RS") (class "Default")
      (node (ref "JP3") (pin "4") (pinfunction "4_4") (pintype "passive"))
      (node (ref "JP6") (pin "RS") (pinfunction "4_RS") (pintype "passive"))
      (node (ref "U2") (pin "39") (pinfunction "P1[25]/MC1A/MAT1[1]_39") (pintype "bidirectional"))
    )
    (net (code "29") (name "/LCD_RST") (class "Default")
      (node (ref "JP2") (pin "3") (pinfunction "3_3") (pintype "passive"))
      (node (ref "JP3") (pin "17") (pinfunction "17_17") (pintype "passive"))
      (node (ref "R4") (pin "1") (pinfunction "1_1") (pintype "passive"))
      (node (ref "S3") (pin "3") (pinfunction "3_3") (pintype "passive"))
      (node (ref "S3") (pin "4") (pinfunction "4_4") (pintype "passive"))
      (node (ref "U2") (pin "20") (pinfunction "P1[31]/SCK1/AD0[5]_20") (pintype "bidirectional"))
    )
    (net (code "30") (name "/LCD_R{slash}W") (class "Default")
      (node (ref "JP3") (pin "5") (pinfunction "5_5") (pintype "passive"))
      (node (ref "JP6") (pin "R/W") (pinfunction "5_R/W") (pintype "passive"))
      (node (ref "U2") (pin "33") (pinfunction "P1[19]/MC0A/USB_PPWR/CAP1[1]_33") (pintype "bidirectional"))
    )
    (net (code "31") (name "/LCD_V") (class "Default")
      (node (ref "C2") (pin "1") (pinfunction "1_1") (pintype "passive"))
      (node (ref "C3") (pin "1") (pinfunction "1_1") (pintype "passive"))
      (node (ref "JP3") (pin "19") (pinfunction "19_19") (pintype "passive"))
      (node (ref "JP3") (pin "2") (pinfunction "2_2") (pintype "passive"))
      (node (ref "JP6") (pin "A") (pinfunction "15_A") (pintype "passive"))
      (node (ref "JP6") (pin "VDD") (pinfunction "2_VDD") (pintype "passive"))
      (node (ref "SJ1") (pin "2") (pinfunction "2_2") (pintype "passive"))
    )
    (net (code "32") (name "/LCD_VO") (class "Default")
      (node (ref "C17") (pin "1") (pinfunction "1_1") (pintype "passive"))
      (node (ref "JP3") (pin "3") (pinfunction "3_3") (pintype "passive"))
      (node (ref "JP6") (pin "VO") (pinfunction "3_VO") (pintype "passive"))
      (node (ref "R24") (pin "2") (pinfunction "2_2") (pintype "passive"))
      (node (ref "U3") (pin "1") (pinfunction "VOUT_1") (pintype "output"))
    )
    (net (code "33") (name "/LCD_VOUT") (class "Default")
      (node (ref "JP3") (pin "18") (pinfunction "18_18") (pintype "passive"))
      (node (ref "SJ6") (pin "3") (pinfunction "3_3") (pintype "passive"))
    )
    (net (code "34") (name "/MISO0") (class "Default")
      (node (ref "JP5") (pin "6") (pinfunction "6_6") (pintype "bidirectional"))
      (node (ref "U2") (pin "61") (pinfunction "P0[17]/CTS1/MISO0/MISO_61") (pintype "bidirectional"))
    )
    (net (code "35") (name "/MISO1") (class "Default")
      (node (ref "R7") (pin "1") (pinfunction "1_1") (pintype "passive"))
      (node (ref "U2") (pin "77") (pinfunction "P0[8]/I2STX_WS/MISO1/MAT2[2]_77") (pintype "bidirectional"))
      (node (ref "W3") (pin "7") (pinfunction "P7_7") (pintype "bidirectional"))
      (node (ref "X4") (pin "7") (pinfunction "DAT0_7") (pintype "bidirectional"))
      (node (ref "X5") (pin "7") (pinfunction "DO_7") (pintype "bidirectional"))
    )
    (net (code "36") (name "/MOSI0") (class "Default")
      (node (ref "JP5") (pin "4") (pinfunction "4_4") (pintype "bidirectional"))
      (node (ref "U2") (pin "60") (pinfunction "P0[18]/DCD1/MOSI0/MOSI_60") (pintype "bidirectional"))
    )
    (net (code "37") (name "/MOSI1") (class "Default")
      (node (ref "R8") (pin "1") (pinfunction "1_1") (pintype "passive"))
      (node (ref "U2") (pin "76") (pinfunction "P0[9]/I2STX_SDA/MOSI1/MAT2[3]_76") (pintype "bidirectional"))
      (node (ref "W3") (pin "8") (pinfunction "P8_8") (pintype "bidirectional"))
      (node (ref "X4") (pin "2") (pinfunction "CMD_2") (pintype "bidirectional"))
      (node (ref "X5") (pin "3") (pinfunction "DI_3") (pintype "bidirectional"))
    )
    (net (code "38") (name "/P0_4") (class "Default")
      (node (ref "U2") (pin "81") (pinfunction "P0[4]/I2SRX_CLK/RD2/CAP2[0]_81") (pintype "bidirectional"))
      (node (ref "W2") (pin "5") (pinfunction "P5_5") (pintype "bidirectional"))
    )
    (net (code "39") (name "/P0_5") (class "Default")
      (node (ref "LED2") (pin "C") (pinfunction "C_C") (pintype "passive"))
      (node (ref "U2") (pin "80") (pinfunction "P0[5]/I2SRX_WS/TD2/CAP2[1]_80") (pintype "bidirectional"))
      (node (ref "W2") (pin "8") (pinfunction "P8_8") (pintype "bidirectional"))
    )
    (net (code "40") (name "/P0_19") (class "Default")
      (node (ref "U2") (pin "59") (pinfunction "P0[19]/DSR1/SDA1_59") (pintype "bidirectional"))
      (node (ref "W2") (pin "4") (pinfunction "P4_4") (pintype "bidirectional"))
    )
    (net (code "41") (name "/P0_20") (class "Default")
      (node (ref "U2") (pin "58") (pinfunction "P0[20]/DTR1/SCL1_58") (pintype "bidirectional"))
      (node (ref "W2") (pin "3") (pinfunction "P3_3") (pintype "bidirectional"))
    )
    (net (code "42") (name "/P0_21") (class "Default")
      (node (ref "U2") (pin "57") (pinfunction "P0[21]/RI1/RD1_57") (pintype "bidirectional"))
      (node (ref "W2") (pin "2") (pinfunction "P2_2") (pintype "bidirectional"))
    )
    (net (code "43") (name "/P0_22") (class "Default")
      (node (ref "U2") (pin "56") (pinfunction "P0[22]/RTS1/TD1_56") (pintype "bidirectional"))
      (node (ref "W2") (pin "1") (pinfunction "P1_1") (pintype "bidirectional"))
    )
    (net (code "44") (name "/P1_0") (class "Default")
      (node (ref "U2") (pin "95") (pinfunction "P1[0]/ENET_TXD0_95") (pintype "bidirectional"))
      (node (ref "W5") (pin "8") (pinfunction "P8_8") (pintype "bidirectional"))
    )
    (net (code "45") (name "/P1_1") (class "Default")
      (node (ref "U2") (pin "94") (pinfunction "P1[1]/ENET_TXD1_94") (pintype "bidirectional"))
      (node (ref "W5") (pin "7") (pinfunction "P7_7") (pintype "bidirectional"))
    )
    (net (code "46") (name "/P1_4") (class "Default")
      (node (ref "U2") (pin "93") (pinfunction "P1[4]/ENET_TX_EN_93") (pintype "bidirectional"))
      (node (ref "W5") (pin "6") (pinfunction "P6_6") (pintype "bidirectional"))
    )
    (net (code "47") (name "/P1_8") (class "Default")
      (node (ref "U2") (pin "92") (pinfunction "P1[8]/ENET_CRS_92") (pintype "bidirectional"))
      (node (ref "W5") (pin "5") (pinfunction "P5_5") (pintype "bidirectional"))
    )
    (net (code "48") (name "/P1_9") (class "Default")
      (node (ref "U2") (pin "91") (pinfunction "P1[9]/ENET_RXD0_91") (pintype "bidirectional"))
      (node (ref "W5") (pin "4") (pinfunction "P4_4") (pintype "bidirectional"))
    )
    (net (code "49") (name "/P1_10") (class "Default")
      (node (ref "U2") (pin "90") (pinfunction "P1[10]/ENET_RXD1_90") (pintype "bidirectional"))
      (node (ref "W5") (pin "3") (pinfunction "P3_3") (pintype "bidirectional"))
    )
    (net (code "50") (name "/P1_14") (class "Default")
      (node (ref "U2") (pin "89") (pinfunction "P1[14]/ENET_RX_ER_89") (pintype "bidirectional"))
      (node (ref "W5") (pin "2") (pinfunction "P2_2") (pintype "bidirectional"))
    )
    (net (code "51") (name "/P1_15") (class "Default")
      (node (ref "U2") (pin "88") (pinfunction "P1[15]/ENET_REF_CLK_88") (pintype "bidirectional"))
      (node (ref "W5") (pin "1") (pinfunction "P1_1") (pintype "bidirectional"))
    )
    (net (code "52") (name "/P1_16") (class "Default")
      (node (ref "U2") (pin "87") (pinfunction "P1[16]/ENET_MDC_87") (pintype "bidirectional"))
      (node (ref "W4") (pin "8") (pinfunction "P8_8") (pintype "bidirectional"))
    )
    (net (code "53") (name "/P1_17") (class "Default")
      (node (ref "U2") (pin "86") (pinfunction "P1[17]/ENET_MDIO_86") (pintype "bidirectional"))
      (node (ref "W4") (pin "7") (pinfunction "P7_7") (pintype "bidirectional"))
    )
    (net (code "54") (name "/P1_21") (class "Default")
      (node (ref "U2") (pin "35") (pinfunction "P1[21]/MCABORT/PWM1[3]/SSEL0_35") (pintype "bidirectional"))
      (node (ref "W1") (pin "7") (pinfunction "P7_7") (pintype "bidirectional"))
    )
    (net (code "55") (name "/P1_22") (class "Default")
      (node (ref "U2") (pin "36") (pinfunction "P1[22]/MC0B/USB_PWRD/MAT1[0]_36") (pintype "bidirectional"))
      (node (ref "W1") (pin "8") (pinfunction "P8_8") (pintype "bidirectional"))
    )
    (net (code "56") (name "/PCAP0") (class "Default")
      (node (ref "U2") (pin "44") (pinfunction "P1[28]/MC2A/PCAP1[0]/MAT0[0]_44") (pintype "bidirectional"))
      (node (ref "W4") (pin "5") (pinfunction "P5_5") (pintype "bidirectional"))
    )
    (net (code "57") (name "/PCAP1") (class "Default")
      (node (ref "U2") (pin "45") (pinfunction "P1[29]/MC2B/PCAP1[1]/MAT0[1]_45") (pintype "bidirectional"))
      (node (ref "W4") (pin "6") (pinfunction "P6_6") (pintype "bidirectional"))
    )
    (net (code "58") (name "/PHA") (class "Default")
      (node (ref "U2") (pin "34") (pinfunction "P1[20]/MCFB0/PWM1[2]/SCK0_34") (pintype "bidirectional"))
      (node (ref "W1") (pin "5") (pinfunction "P5_5") (pintype "bidirectional"))
    )
    (net (code "59") (name "/PHB") (class "Default")
      (node (ref "U2") (pin "37") (pinfunction "P1[23]/MCFB1/PWM1[4]/MISO0_37") (pintype "bidirectional"))
      (node (ref "W1") (pin "6") (pinfunction "P6_6") (pintype "bidirectional"))
    )
    (net (code "60") (name "/PWM5") (class "Default")
      (node (ref "U2") (pin "38") (pinfunction "P1[24]/MCFB2/PWM1[5]/MOSI0_38") (pintype "bidirectional"))
      (node (ref "W4") (pin "3") (pinfunction "P3_3") (pintype "bidirectional"))
    )
    (net (code "61") (name "/PWM6") (class "Default")
      (node (ref "U2") (pin "40") (pinfunction "P1[26]/MC1B/PWM1[6]/CAP0[0]_40") (pintype "bidirectional"))
      (node (ref "W4") (pin "4") (pinfunction "P4_4") (pintype "bidirectional"))
    )
    (net (code "62") (name "/RESET") (class "Default")
      (node (ref "JP2") (pin "1") (pinfunction "1_1") (pintype "passive"))
      (node (ref "R2") (pin "1") (pinfunction "1_1") (pintype "passive"))
      (node (ref "S1") (pin "3") (pinfunction "3_3") (pintype "passive"))
      (node (ref "S1") (pin "4") (pinfunction "4_4") (pintype "passive"))
      (node (ref "U2") (pin "17") (pinfunction "RESET_17") (pintype "bidirectional"))
    )
    (net (code "63") (name "/RXD0") (class "Default")
      (node (ref "JP4") (pin "4") (pinfunction "4_4") (pintype "passive"))
      (node (ref "U2") (pin "99") (pinfunction "P0[3]/RXD0/AD0[6]_99") (pintype "bidirectional"))
    )
    (net (code "64") (name "/RXD2") (class "Default")
      (node (ref "U2") (pin "49") (pinfunction "P0[11]/RXD2/SCL2/MAT3[1]_49") (pintype "bidirectional"))
      (node (ref "W4") (pin "2") (pinfunction "P2_2") (pintype "bidirectional"))
    )
    (net (code "65") (name "/RXD3") (class "Default")
      (node (ref "U2") (pin "85") (pinfunction "P4[29]/TX_MCLK/MAT2[1]/RXD3_85") (pintype "bidirectional"))
      (node (ref "W3") (pin "2") (pinfunction "P2_2") (pintype "bidirectional"))
    )
    (net (code "66") (name "/SCK0") (class "Default")
      (node (ref "JP5") (pin "5") (pinfunction "5_5") (pintype "bidirectional"))
      (node (ref "U2") (pin "62") (pinfunction "P0[15]/TXD1/SCK0/SCK_62") (pintype "bidirectional"))
    )
    (net (code "67") (name "/SCK1") (class "Default")
      (node (ref "U2") (pin "78") (pinfunction "P0[7]/I2STX_CLK/SCK1/MAT2[1]_78") (pintype "bidirectional"))
      (node (ref "W3") (pin "6") (pinfunction "P6_6") (pintype "bidirectional"))
      (node (ref "X4") (pin "5") (pinfunction "CLK_5") (pintype "bidirectional"))
      (node (ref "X5") (pin "5") (pinfunction "SCK_5") (pintype "bidirectional"))
    )
    (net (code "68") (name "/SCL0") (class "Default")
      (node (ref "PCB1") (pin "3") (pinfunction "SCL_3") (pintype "bidirectional"))
      (node (ref "R13") (pin "1") (pinfunction "1_1") (pintype "passive"))
      (node (ref "U2") (pin "24") (pinfunction "P0[28]/SCL0/USB_SCL_24") (pintype "bidirectional"))
      (node (ref "W3") (pin "3") (pinfunction "P3_3") (pintype "bidirectional"))
    )
    (net (code "69") (name "/SCL1") (class "Default")
      (node (ref "SJ7") (pin "1") (pinfunction "1_1") (pintype "passive"))
      (node (ref "U2") (pin "47") (pinfunction "P0[1]/TD1/RXD3/SCL1_47") (pintype "bidirectional"))
      (node (ref "W2") (pin "6") (pinfunction "P6_6") (pintype "bidirectional"))
    )
    (net (code "70") (name "/SDA0") (class "Default")
      (node (ref "PCB1") (pin "6") (pinfunction "SDA_6") (pintype "bidirectional"))
      (node (ref "R14") (pin "1") (pinfunction "1_1") (pintype "passive"))
      (node (ref "U2") (pin "25") (pinfunction "P0[27]/SDA0/USB_SDA_25") (pintype "bidirectional"))
      (node (ref "W3") (pin "4") (pinfunction "P4_4") (pintype "bidirectional"))
    )
    (net (code "71") (name "/SDA1") (class "Default")
      (node (ref "SJ8") (pin "1") (pinfunction "1_1") (pintype "passive"))
      (node (ref "U2") (pin "46") (pinfunction "P0[0]/RD1/TXD3/SDA1_46") (pintype "bidirectional"))
      (node (ref "W2") (pin "7") (pinfunction "P7_7") (pintype "bidirectional"))
    )
    (net (code "72") (name "/SD_CD") (class "Default")
      (node (ref "TP5") (pin "1") (pinfunction "TP_1") (pintype "bidirectional"))
      (node (ref "U2") (pin "51") (pinfunction "P2[12]/EINT2/I2STX_WS_51") (pintype "bidirectional"))
      (node (ref "X4") (pin "CD") (pinfunction "CD_CD") (pintype "bidirectional"))
      (node (ref "X5") (pin "CD1") (pinfunction "SHIELD_CD1") (pintype "bidirectional"))
      (node (ref "X5") (pin "CD2") (pinfunction "SHIELD_CD2") (pintype "bidirectional"))
    )
    (net (code "73") (name "/SD_WP") (class "Default")
      (node (ref "TP6") (pin "1") (pinfunction "TP_1") (pintype "bidirectional"))
      (node (ref "U2") (pin "50") (pinfunction "P2[13]/EINT3/I2STX_SDA_50") (pintype "bidirectional"))
      (node (ref "X4") (pin "WP") (pinfunction "WP_WP") (pintype "bidirectional"))
    )
    (net (code "74") (name "/SSEL0") (class "Default")
      (node (ref "JP5") (pin "3") (pinfunction "3_3") (pintype "bidirectional"))
      (node (ref "U2") (pin "63") (pinfunction "P0[16]/RXD1/SSEL0/SSEL_63") (pintype "bidirectional"))
    )
    (net (code "75") (name "/SSEL1") (class "Default")
      (node (ref "R9") (pin "1") (pinfunction "1_1") (pintype "passive"))
      (node (ref "U2") (pin "79") (pinfunction "P0[6]/I2SRX_SDA/SSEL1/MAT2[0]_79") (pintype "bidirectional"))
      (node (ref "X4") (pin "1") (pinfunction "CD/DAT3_1") (pintype "bidirectional"))
      (node (ref "X5") (pin "2") (pinfunction "CS_2") (pintype "bidirectional"))
    )
    (net (code "76") (name "/SSEL1_A") (class "Default")
      (node (ref "U2") (pin "65") (pinfunction "P2[8]/TD2/TXD2_65") (pintype "bidirectional"))
      (node (ref "W3") (pin "5") (pinfunction "P5_5") (pintype "bidirectional"))
    )
    (net (code "77") (name "/TCK") (class "Default")
      (node (ref "JTAG1") (pin "4") (pinfunction "4_4") (pintype "passive"))
      (node (ref "U2") (pin "5") (pinfunction "TCK/SWDCLK_5") (pintype "bidirectional"))
    )
    (net (code "78") (name "/TDI") (class "Default")
      (node (ref "JTAG1") (pin "8") (pinfunction "8_8") (pintype "passive"))
      (node (ref "U2") (pin "2") (pinfunction "TDI_2") (pintype "bidirectional"))
    )
    (net (code "79") (name "/TDO") (class "Default")
      (node (ref "JTAG1") (pin "6") (pinfunction "6_6") (pintype "passive"))
      (node (ref "U2") (pin "1") (pinfunction "TDO/SWO_1") (pintype "bidirectional"))
    )
    (net (code "80") (name "/TMS") (class "Default")
      (node (ref "JTAG1") (pin "2") (pinfunction "2_2") (pintype "passive"))
      (node (ref "U2") (pin "3") (pinfunction "TMS/SWDIO_3") (pintype "bidirectional"))
    )
    (net (code "81") (name "/TXD0") (class "Default")
      (node (ref "JP4") (pin "5") (pinfunction "5_5") (pintype "passive"))
      (node (ref "U2") (pin "98") (pinfunction "P0[2]/TXD0/AD0[7]_98") (pintype "bidirectional"))
    )
    (net (code "82") (name "/TXD2") (class "Default")
      (node (ref "U2") (pin "48") (pinfunction "P0[10]/TXD2/SDA2/MAT3[0]_48") (pintype "bidirectional"))
      (node (ref "W4") (pin "1") (pinfunction "P1_1") (pintype "bidirectional"))
    )
    (net (code "83") (name "/TXD3") (class "Default")
      (node (ref "U2") (pin "82") (pinfunction "P4[28]/RX_MCLK/MAT2[0]/TXD3_82") (pintype "bidirectional"))
      (node (ref "W3") (pin "1") (pinfunction "P1_1") (pintype "bidirectional"))
    )
    (net (code "84") (name "/USB_CONNECT") (class "Default")
      (node (ref "R15") (pin "1") (pinfunction "1_1") (pintype "passive"))
      (node (ref "TP3") (pin "1") (pinfunction "TP_1") (pintype "bidirectional"))
      (node (ref "U2") (pin "64") (pinfunction "P2[9]/USB_CONNECT/RXD2_64") (pintype "bidirectional"))
    )
    (net (code "85") (name "/USB_DM") (class "Default")
      (node (ref "C19") (pin "1") (pinfunction "1_1") (pintype "passive"))
      (node (ref "R19") (pin "1") (pinfunction "1_1") (pintype "passive"))
      (node (ref "U2") (pin "30") (pinfunction "P0[30]/USB_D-_30") (pintype "bidirectional"))
    )
    (net (code "86") (name "/USB_DP") (class "Default")
      (node (ref "C18") (pin "1") (pinfunction "1_1") (pintype "passive"))
      (node (ref "R16") (pin "1") (pinfunction "1_1") (pintype "passive"))
      (node (ref "U2") (pin "29") (pinfunction "P0[29]/USB_D+_29") (pintype "bidirectional"))
    )
    (net (code "87") (name "/USB_ID") (class "Default")
      (node (ref "X2") (pin "ID") (pinfunction "ID_ID") (pintype "bidirectional"))
      (node (ref "X3") (pin "4") (pinfunction "ID_4") (pintype "bidirectional"))
    )
    (net (code "88") (name "/USB_VBUS") (class "Default")
      (node (ref "R22") (pin "1") (pinfunction "1_1") (pintype "passive"))
      (node (ref "TP1") (pin "1") (pinfunction "TP_1") (pintype "bidirectional"))
      (node (ref "U2") (pin "21") (pinfunction "P1[30]/VBUS/AD0[4]_21") (pintype "bidirectional"))
    )
    (net (code "89") (name "/VBUS") (class "Default")
      (node (ref "D1") (pin "A") (pinfunction "A_A") (pintype "passive"))
      (node (ref "R22") (pin "2") (pinfunction "2_2") (pintype "passive"))
      (node (ref "X1") (pin "VBUS") (pinfunction "VBUS_VBUS") (pintype "bidirectional"))
      (node (ref "X2") (pin "VBUS") (pinfunction "VBUS_VBUS") (pintype "bidirectional"))
      (node (ref "X3") (pin "1") (pinfunction "VCC_1") (pintype "bidirectional"))
    )
    (net (code "90") (name "/VI2C") (class "Default")
      (node (ref "C13") (pin "1") (pinfunction "1_1") (pintype "passive"))
      (node (ref "PCB1") (pin "4") (pinfunction "VCC_4") (pintype "power_in"))
      (node (ref "R12") (pin "2") (pinfunction "2_2") (pintype "passive"))
      (node (ref "R13") (pin "2") (pinfunction "2_2") (pintype "passive"))
      (node (ref "R14") (pin "2") (pinfunction "2_2") (pintype "passive"))
      (node (ref "SJ2") (pin "2") (pinfunction "2_2") (pintype "passive"))
    )
    (net (code "91") (name "/VIN") (class "Default")
      (node (ref "D2") (pin "A") (pinfunction "A_A") (pintype "passive"))
      (node (ref "JP1") (pin "1") (pinfunction "1_1") (pintype "passive"))
      (node (ref "Z1") (pin "1") (pinfunction "1_1") (pintype "passive"))
    )
    (net (code "92") (name "/VSPI") (class "Default")
      (node (ref "JP5") (pin "1") (pinfunction "1_1") (pintype "bidirectional"))
      (node (ref "SJ5") (pin "2") (pinfunction "2_2") (pintype "passive"))
    )
    (net (code "93") (name "/VUART") (class "Default")
      (node (ref "JP4") (pin "3") (pinfunction "3_3") (pintype "passive"))
      (node (ref "SJ4") (pin "2") (pinfunction "2_2") (pintype "passive"))
    )
    (net (code "94") (name "/XTAL1") (class "Default")
      (node (ref "C14") (pin "1") (pinfunction "1_1") (pintype "passive"))
      (node (ref "U2") (pin "22") (pinfunction "XTAL1_22") (pintype "bidirectional"))
      (node (ref "Y1") (pin "2") (pinfunction "2_2") (pintype "passive"))
    )
    (net (code "95") (name "/XTAL2") (class "Default")
      (node (ref "C15") (pin "1") (pinfunction "1_1") (pintype "passive"))
      (node (ref "U2") (pin "23") (pinfunction "XTAL2_23") (pintype "bidirectional"))
      (node (ref "Y1") (pin "1") (pinfunction "1_1") (pintype "passive"))
    )
    (net (code "96") (name "/~{RSTOUT}") (class "Default")
      (node (ref "U2") (pin "14") (pinfunction "RSTOUT_14") (pintype "bidirectional"))
    )
    (net (code "97") (name "/~{TRST}") (class "Default")
      (node (ref "JTAG1") (pin "10") (pinfunction "10_10") (pintype "passive"))
      (node (ref "U2") (pin "4") (pinfunction "TRST_4") (pintype "bidirectional"))
    )
    (net (code "98") (name "Net-(JP3-Pad20)") (class "Default")
      (node (ref "JP3") (pin "20") (pinfunction "20_20") (pintype "passive"))
      (node (ref "R11") (pin "1") (pinfunction "1_1") (pintype "passive"))
    )
    (net (code "99") (name "Net-(JP3-Pad21)") (class "Default")
      (node (ref "JP3") (pin "21") (pinfunction "21_21") (pintype "passive"))
      (node (ref "R10") (pin "1") (pinfunction "1_1") (pintype "passive"))
    )
    (net (code "100") (name "Net-(JP3-Pad22)") (class "Default")
      (node (ref "JP3") (pin "22") (pinfunction "22_22") (pintype "passive"))
      (node (ref "R6") (pin "1") (pinfunction "1_1") (pintype "passive"))
    )
    (net (code "101") (name "Net-(JP6-16)") (class "Default")
      (node (ref "JP6") (pin "R") (pinfunction "16_R") (pintype "passive"))
      (node (ref "R21") (pin "1") (pinfunction "1_1") (pintype "passive"))
    )
    (net (code "102") (name "Net-(JP6-17)") (class "Default")
      (node (ref "JP6") (pin "G") (pinfunction "17_G") (pintype "passive"))
      (node (ref "R20") (pin "1") (pinfunction "1_1") (pintype "passive"))
    )
    (net (code "103") (name "Net-(JP6-18)") (class "Default")
      (node (ref "JP6") (pin "B") (pinfunction "18_B") (pintype "passive"))
      (node (ref "R18") (pin "1") (pinfunction "1_1") (pintype "passive"))
    )
    (net (code "104") (name "Net-(LED1-PadA)") (class "Default")
      (node (ref "LED1") (pin "A") (pinfunction "A_A") (pintype "passive"))
      (node (ref "R1") (pin "2") (pinfunction "2_2") (pintype "passive"))
    )
    (net (code "105") (name "Net-(LED2-PadA)") (class "Default")
      (node (ref "LED2") (pin "A") (pinfunction "A_A") (pintype "passive"))
      (node (ref "R5") (pin "2") (pinfunction "2_2") (pintype "passive"))
    )
    (net (code "106") (name "Net-(Q1-B)") (class "Default")
      (node (ref "Q1") (pin "1") (pinfunction "B_1") (pintype "passive"))
      (node (ref "R15") (pin "2") (pinfunction "2_2") (pintype "passive"))
      (node (ref "R17") (pin "1") (pinfunction "1_1") (pintype "passive"))
    )
    (net (code "107") (name "Net-(Q1-C)") (class "Default")
      (node (ref "Q1") (pin "3") (pinfunction "C_3") (pintype "passive"))
      (node (ref "R23") (pin "1") (pinfunction "1_1") (pintype "passive"))
    )
    (net (code "108") (name "Net-(U3-SCL)") (class "Default")
      (node (ref "SJ7") (pin "2") (pinfunction "2_2") (pintype "passive"))
      (node (ref "U3") (pin "5") (pinfunction "SCL_5") (pintype "bidirectional"))
    )
    (net (code "109") (name "Net-(U3-SDA)") (class "Default")
      (node (ref "SJ8") (pin "2") (pinfunction "2_2") (pintype "passive"))
      (node (ref "U3") (pin "4") (pinfunction "SDA_4") (pintype "bidirectional"))
    )
    (net (code "110") (name "unconnected-(JP3-Pad16)") (class "Default")
      (node (ref "JP3") (pin "16") (pinfunction "16_16") (pintype "passive"))
    )
    (net (code "111") (name "unconnected-(JP4-Pad2)") (class "Default")
      (node (ref "JP4") (pin "2") (pinfunction "2_2") (pintype "passive"))
    )
    (net (code "112") (name "unconnected-(JP4-Pad6)") (class "Default")
      (node (ref "JP4") (pin "6") (pinfunction "6_6") (pintype "passive"))
    )
    (net (code "113") (name "unconnected-(JTAG1-Pad7)") (class "Default")
      (node (ref "JTAG1") (pin "7") (pinfunction "7_7") (pintype "passive"))
    )
    (net (code "114") (name "unconnected-(U2-N.C.-Pad13)") (class "Default")
      (node (ref "U2") (pin "13") (pinfunction "N.C._13") (pintype "no_connect"))
    )
    (net (code "115") (name "unconnected-(U2-RTCK-Pad100)") (class "Default")
      (node (ref "U2") (pin "100") (pinfunction "RTCK_100") (pintype "bidirectional"))
    )
    (net (code "116") (name "unconnected-(U2-RTCX1-Pad16)") (class "Default")
      (node (ref "U2") (pin "16") (pinfunction "RTCX1_16") (pintype "bidirectional"))
    )
    (net (code "117") (name "unconnected-(U2-RTCX2-Pad18)") (class "Default")
      (node (ref "U2") (pin "18") (pinfunction "RTCX2_18") (pintype "bidirectional"))
    )
    (net (code "118") (name "unconnected-(W1-2.5V-Pad10)") (class "Default")
      (node (ref "W1") (pin "10") (pinfunction "2.5V_10") (pintype "bidirectional"))
    )
    (net (code "119") (name "unconnected-(W2-2.5V-Pad10)") (class "Default")
      (node (ref "W2") (pin "10") (pinfunction "2.5V_10") (pintype "bidirectional"))
    )
    (net (code "120") (name "unconnected-(W3-2.5V-Pad10)") (class "Default")
      (node (ref "W3") (pin "10") (pinfunction "2.5V_10") (pintype "bidirectional"))
    )
    (net (code "121") (name "unconnected-(W4-2.5V-Pad10)") (class "Default")
      (node (ref "W4") (pin "10") (pinfunction "2.5V_10") (pintype "bidirectional"))
    )
    (net (code "122") (name "unconnected-(W5-2.5V-Pad10)") (class "Default")
      (node (ref "W5") (pin "10") (pinfunction "2.5V_10") (pintype "bidirectional"))
    )
    (net (code "123") (name "unconnected-(X2-MTN1-PadMTN3)") (class "Default")
      (node (ref "X2") (pin "MTN3") (pinfunction "MTN1_MTN3") (pintype "bidirectional"))
    )
    (net (code "124") (name "unconnected-(X2-MTN2-PadMTN1)") (class "Default")
      (node (ref "X2") (pin "MTN1") (pinfunction "MTN2_MTN1") (pintype "bidirectional"))
    )
    (net (code "125") (name "unconnected-(X2-MTN3-PadMTN2)") (class "Default")
      (node (ref "X2") (pin "MTN2") (pinfunction "MTN3_MTN2") (pintype "bidirectional"))
    )
    (net (code "126") (name "unconnected-(X2-PadMTN4)") (class "Default")
      (node (ref "X2") (pin "MTN4") (pinfunction "MTN4_MTN4") (pintype "bidirectional"))
    )
    (net (code "127") (name "unconnected-(X4-DAT1-Pad8)") (class "Default")
      (node (ref "X4") (pin "8") (pinfunction "DAT1_8") (pintype "bidirectional"))
    )
    (net (code "128") (name "unconnected-(X4-DAT2-Pad9)") (class "Default")
      (node (ref "X4") (pin "9") (pinfunction "DAT2_9") (pintype "bidirectional"))
    )
    (net (code "129") (name "unconnected-(X5-NC-Pad1)") (class "Default")
      (node (ref "X5") (pin "1") (pinfunction "NC_1") (pintype "bidirectional"))
    )
    (net (code "130") (name "unconnected-(X5-RSV-Pad8)") (class "Default")
      (node (ref "X5") (pin "8") (pinfunction "RSV_8") (pintype "bidirectional"))
    )
  )
)
